# analogControlBoardV1_3.net
KiCad netlist of a schematic drawn in EAGLE
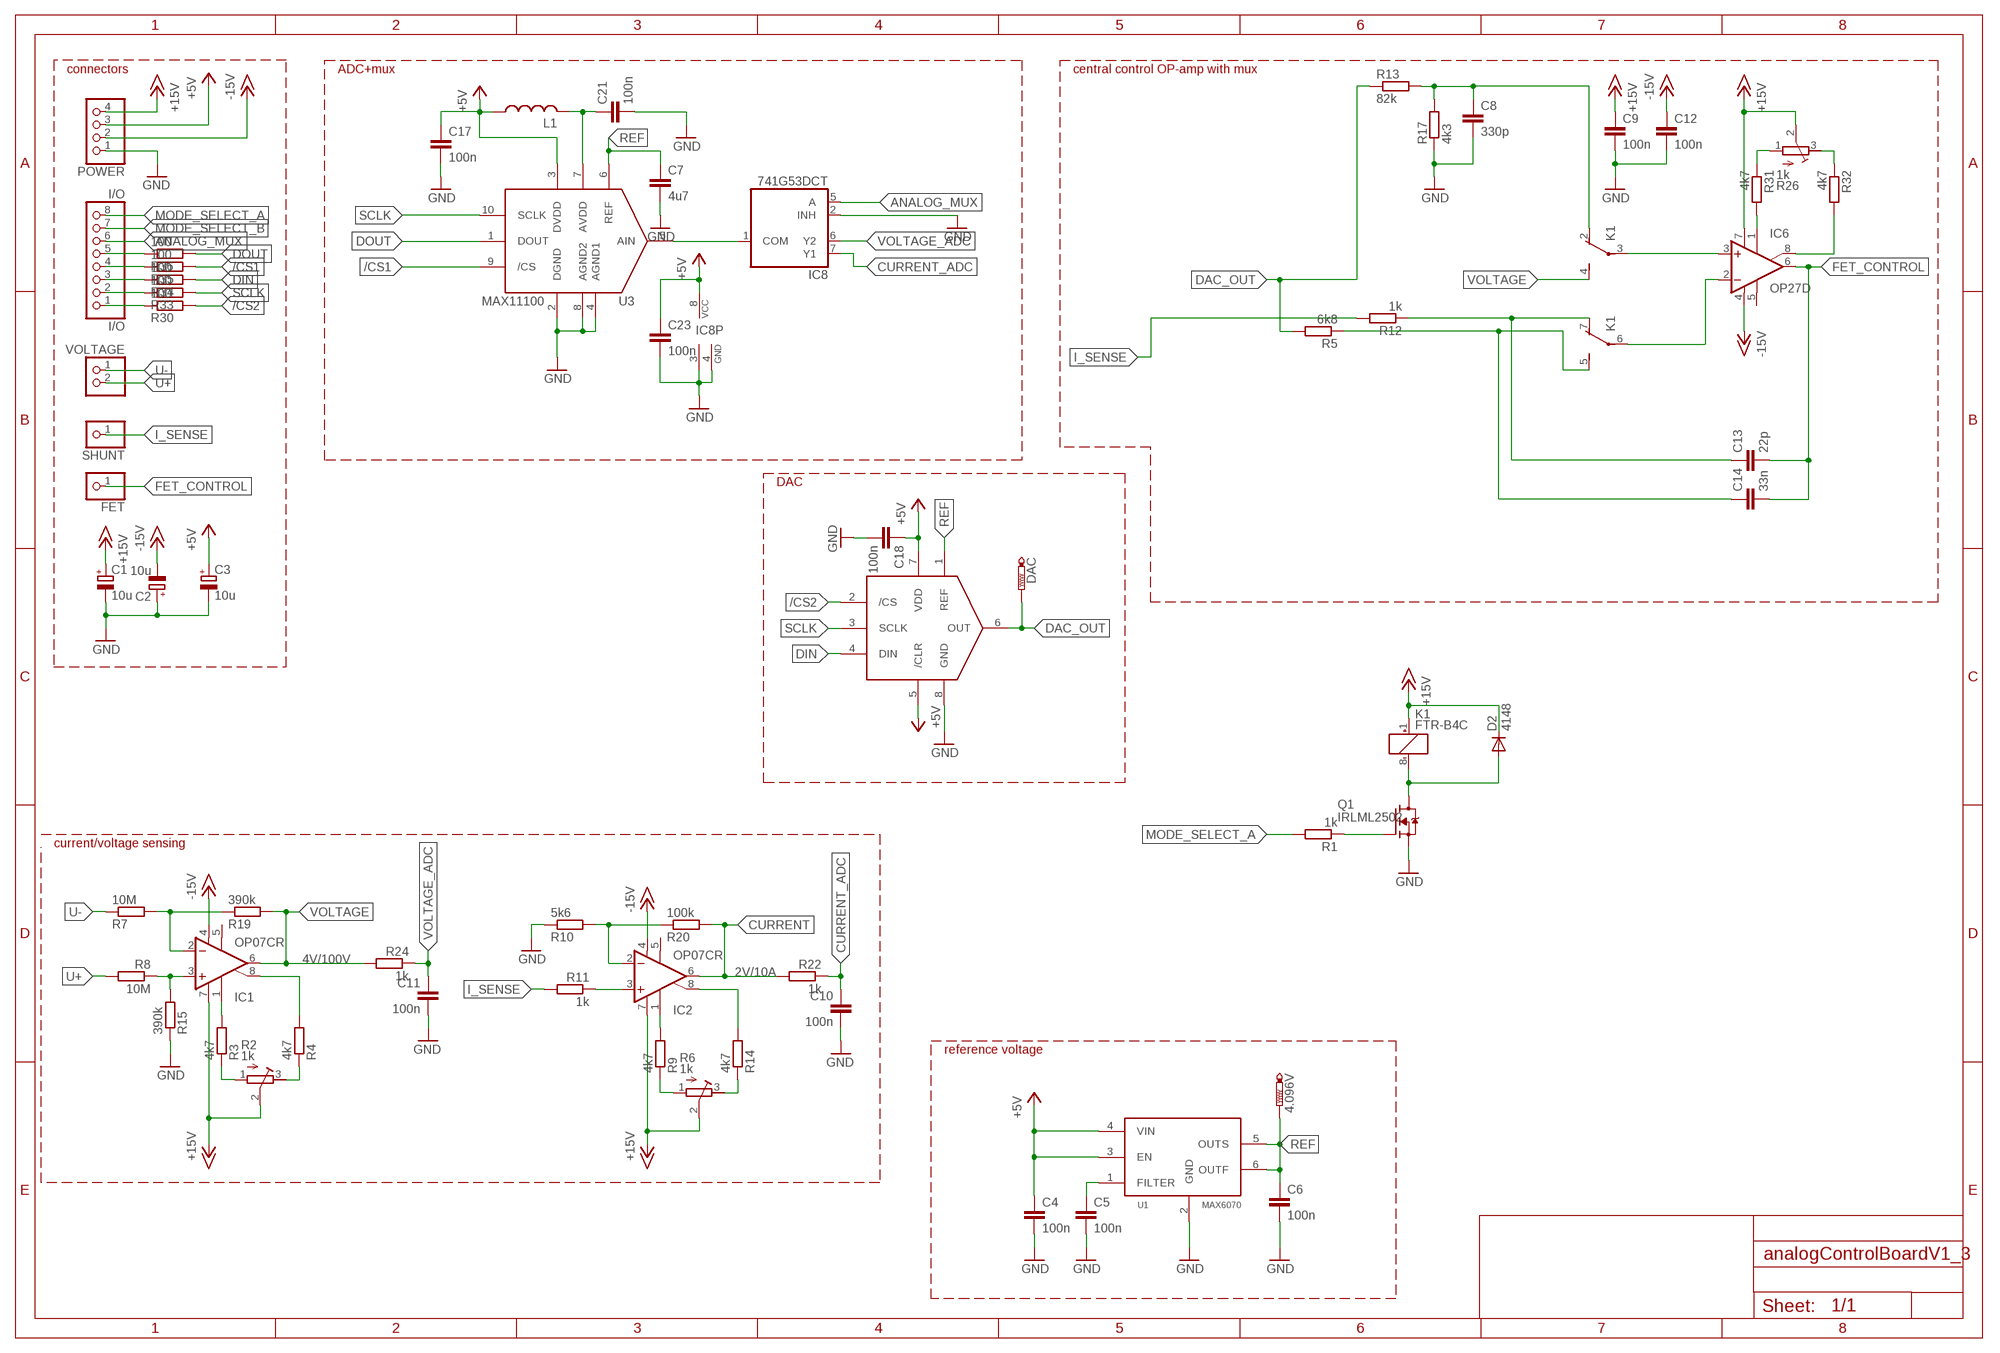
[diagram p0: schematic, sheet 1]

(export (version "E")
  (design (tool "Eeschema 10.0.6"))
  (components
    (comp (ref "4.096V")
      (value "PTR1TP14R")
      (footprint "eagle-import:TP14R")
      (libsource (lib "eagle-import") (part "PTR1TP14R"))
    )
    (comp (ref "C1")
      (value "10u")
      (footprint "eagle-import:153CLV-0505")
      (libsource (lib "eagle-import") (part "CPOL-EU153CLV-0505"))
    )
    (comp (ref "C2")
      (value "10u")
      (footprint "eagle-import:153CLV-0505")
      (libsource (lib "eagle-import") (part "CPOL-EU153CLV-0505"))
    )
    (comp (ref "C3")
      (value "10u")
      (footprint "eagle-import:153CLV-0505")
      (libsource (lib "eagle-import") (part "CPOL-EU153CLV-0505"))
    )
    (comp (ref "C4")
      (value "100n")
      (footprint "eagle-import:C0603K")
      (libsource (lib "eagle-import") (part "C-EUC0603K"))
    )
    (comp (ref "C5")
      (value "100n")
      (footprint "eagle-import:C0603K")
      (libsource (lib "eagle-import") (part "C-EUC0603K"))
    )
    (comp (ref "C6")
      (value "100n")
      (footprint "eagle-import:C0603K")
      (libsource (lib "eagle-import") (part "C-EUC0603K"))
    )
    (comp (ref "C7")
      (value "4u7")
      (footprint "eagle-import:C0805")
      (libsource (lib "eagle-import") (part "C-EUC0805"))
    )
    (comp (ref "C8")
      (value "330p")
      (footprint "eagle-import:C0603K")
      (libsource (lib "eagle-import") (part "C-EUC0603K"))
    )
    (comp (ref "C9")
      (value "100n")
      (footprint "eagle-import:C0603K")
      (libsource (lib "eagle-import") (part "C-EUC0603K"))
    )
    (comp (ref "C10")
      (value "100n")
      (footprint "eagle-import:C0603K")
      (libsource (lib "eagle-import") (part "C-EUC0603K"))
    )
    (comp (ref "C11")
      (value "100n")
      (footprint "eagle-import:C0603K")
      (libsource (lib "eagle-import") (part "C-EUC0603K"))
    )
    (comp (ref "C12")
      (value "100n")
      (footprint "eagle-import:C0603K")
      (libsource (lib "eagle-import") (part "C-EUC0603K"))
    )
    (comp (ref "C13")
      (value "22p")
      (footprint "eagle-import:C0603K")
      (libsource (lib "eagle-import") (part "C-EUC0603K"))
    )
    (comp (ref "C14")
      (value "33n")
      (footprint "eagle-import:C0603K")
      (libsource (lib "eagle-import") (part "C-EUC0603K"))
    )
    (comp (ref "C17")
      (value "100n")
      (footprint "eagle-import:C0603K")
      (libsource (lib "eagle-import") (part "C-EUC0603K"))
    )
    (comp (ref "C18")
      (value "100n")
      (footprint "eagle-import:C0603K")
      (libsource (lib "eagle-import") (part "C-EUC0603K"))
    )
    (comp (ref "C21")
      (value "100n")
      (footprint "eagle-import:C0603K")
      (libsource (lib "eagle-import") (part "C-EUC0603K"))
    )
    (comp (ref "C23")
      (value "100n")
      (footprint "eagle-import:C0603K")
      (libsource (lib "eagle-import") (part "C-EUC0603K"))
    )
    (comp (ref "D2")
      (value "4148")
      (footprint "eagle-import:SOD123")
      (libsource (lib "eagle-import") (part "DIODE-SOD123"))
    )
    (comp (ref "DAC")
      (value "PTR1TP14R")
      (footprint "eagle-import:TP14R")
      (libsource (lib "eagle-import") (part "PTR1TP14R"))
    )
    (comp (ref "FET")
      (value "PINHD-1X1")
      (footprint "eagle-import:1X01")
      (libsource (lib "eagle-import") (part "PINHD-1X1"))
    )
    (comp (ref "I/O")
      (value "I/O")
      (footprint "eagle-import:1X08")
      (libsource (lib "eagle-import") (part "PINHD-1X8"))
    )
    (comp (ref "IC1")
      (value "OP07CR")
      (footprint "eagle-import:SO08")
      (libsource (lib "eagle-import") (part "OP07RC"))
    )
    (comp (ref "IC2")
      (value "OP07CR")
      (footprint "eagle-import:SO08")
      (libsource (lib "eagle-import") (part "OP07RC"))
    )
    (comp (ref "IC6")
      (value "OP27D")
      (footprint "eagle-import:SO08")
      (libsource (lib "eagle-import") (part "OP27D"))
    )
    (comp (ref "IC8")
      (value "741G53DCT")
      (footprint "eagle-import:DCT_R-PDSO-G8")
      (libsource (lib "eagle-import") (part "741G53DCT"))
    )
    (comp (ref "K1")
      (value "FTR-B4C")
      (footprint "eagle-import:FTR-B4C")
      (libsource (lib "eagle-import") (part "FTR-B4C"))
    )
    (comp (ref "L1")
      (value "INDUCTOR0603")
      (footprint "eagle-import:R0603")
      (libsource (lib "eagle-import") (part "INDUCTOR0603"))
    )
    (comp (ref "POWER")
      (value "PINHD-1X4")
      (footprint "eagle-import:1X04")
      (libsource (lib "eagle-import") (part "PINHD-1X4"))
    )
    (comp (ref "Q1")
      (value "IRLML2502")
      (footprint "eagle-import:SOT23-3")
      (libsource (lib "eagle-import") (part "IRLML2502"))
    )
    (comp (ref "R1")
      (value "1k")
      (footprint "eagle-import:R0603")
      (libsource (lib "eagle-import") (part "R-EU_R0603"))
    )
    (comp (ref "R2")
      (value "1k")
      (footprint "eagle-import:RTRIM64W")
      (libsource (lib "eagle-import") (part "R-TRIMM64W"))
    )
    (comp (ref "R3")
      (value "4k7")
      (footprint "eagle-import:R0603")
      (libsource (lib "eagle-import") (part "R-EU_R0603"))
    )
    (comp (ref "R4")
      (value "4k7")
      (footprint "eagle-import:R0603")
      (libsource (lib "eagle-import") (part "R-EU_R0603"))
    )
    (comp (ref "R5")
      (value "6k8")
      (footprint "eagle-import:R0603")
      (libsource (lib "eagle-import") (part "R-EU_R0603"))
    )
    (comp (ref "R6")
      (value "1k")
      (footprint "eagle-import:RTRIM64W")
      (libsource (lib "eagle-import") (part "R-TRIMM64W"))
    )
    (comp (ref "R7")
      (value "10M")
      (footprint "eagle-import:R0603")
      (libsource (lib "eagle-import") (part "R-EU_R0603"))
    )
    (comp (ref "R8")
      (value "10M")
      (footprint "eagle-import:R0603")
      (libsource (lib "eagle-import") (part "R-EU_R0603"))
    )
    (comp (ref "R9")
      (value "4k7")
      (footprint "eagle-import:R0603")
      (libsource (lib "eagle-import") (part "R-EU_R0603"))
    )
    (comp (ref "R10")
      (value "5k6")
      (footprint "eagle-import:R0603")
      (libsource (lib "eagle-import") (part "R-EU_R0603"))
    )
    (comp (ref "R11")
      (value "1k")
      (footprint "eagle-import:R0603")
      (libsource (lib "eagle-import") (part "R-EU_R0603"))
    )
    (comp (ref "R12")
      (value "1k")
      (footprint "eagle-import:R0603")
      (libsource (lib "eagle-import") (part "R-EU_R0603"))
    )
    (comp (ref "R13")
      (value "82k")
      (footprint "eagle-import:R0603")
      (libsource (lib "eagle-import") (part "R-EU_R0603"))
    )
    (comp (ref "R14")
      (value "4k7")
      (footprint "eagle-import:R0603")
      (libsource (lib "eagle-import") (part "R-EU_R0603"))
    )
    (comp (ref "R15")
      (value "390k")
      (footprint "eagle-import:R0603")
      (libsource (lib "eagle-import") (part "R-EU_R0603"))
    )
    (comp (ref "R17")
      (value "4k3")
      (footprint "eagle-import:R0603")
      (libsource (lib "eagle-import") (part "R-EU_R0603"))
    )
    (comp (ref "R19")
      (value "390k")
      (footprint "eagle-import:R0603")
      (libsource (lib "eagle-import") (part "R-EU_R0603"))
    )
    (comp (ref "R20")
      (value "100k")
      (footprint "eagle-import:R0603")
      (libsource (lib "eagle-import") (part "R-EU_R0603"))
    )
    (comp (ref "R22")
      (value "1k")
      (footprint "eagle-import:R0603")
      (libsource (lib "eagle-import") (part "R-EU_R0603"))
    )
    (comp (ref "R24")
      (value "1k")
      (footprint "eagle-import:R0603")
      (libsource (lib "eagle-import") (part "R-EU_R0603"))
    )
    (comp (ref "R26")
      (value "1k")
      (footprint "eagle-import:RTRIM64W")
      (libsource (lib "eagle-import") (part "R-TRIMM64W"))
    )
    (comp (ref "R30")
      (value "100")
      (footprint "eagle-import:R0603")
      (libsource (lib "eagle-import") (part "R-EU_R0603"))
    )
    (comp (ref "R31")
      (value "4k7")
      (footprint "eagle-import:R0603")
      (libsource (lib "eagle-import") (part "R-EU_R0603"))
    )
    (comp (ref "R32")
      (value "4k7")
      (footprint "eagle-import:R0603")
      (libsource (lib "eagle-import") (part "R-EU_R0603"))
    )
    (comp (ref "R33")
      (value "100")
      (footprint "eagle-import:R0603")
      (libsource (lib "eagle-import") (part "R-EU_R0603"))
    )
    (comp (ref "R34")
      (value "100")
      (footprint "eagle-import:R0603")
      (libsource (lib "eagle-import") (part "R-EU_R0603"))
    )
    (comp (ref "R35")
      (value "100")
      (footprint "eagle-import:R0603")
      (libsource (lib "eagle-import") (part "R-EU_R0603"))
    )
    (comp (ref "R36")
      (value "100")
      (footprint "eagle-import:R0603")
      (libsource (lib "eagle-import") (part "R-EU_R0603"))
    )
    (comp (ref "SHUNT")
      (value "PINHD-1X1")
      (footprint "eagle-import:1X01")
      (libsource (lib "eagle-import") (part "PINHD-1X1"))
    )
    (comp (ref "U1")
      (value "MAX6070")
      (footprint "eagle-import:SOT23-6L")
      (libsource (lib "eagle-import") (part "MAX6070"))
    )
    (comp (ref "U2")
      (value "MAX5216")
      (footprint "eagle-import:UMAX8")
      (libsource (lib "eagle-import") (part "MAX5216"))
    )
    (comp (ref "U3")
      (value "MAX11100")
      (footprint "eagle-import:UMAX10")
      (libsource (lib "eagle-import") (part "MAX11100"))
    )
    (comp (ref "VOLTAGE")
      (value "PINHD-1X2")
      (footprint "eagle-import:1X02")
      (libsource (lib "eagle-import") (part "PINHD-1X2"))
    )
  )
  (nets
    (net (code "1") (name "+5V") (class "Default")
      (node (ref "C17") (pin "1") (pinfunction "1_1") (pintype "passive"))
      (node (ref "C18") (pin "1") (pinfunction "1_1") (pintype "passive"))
      (node (ref "C23") (pin "1") (pinfunction "1_1") (pintype "passive"))
      (node (ref "C3") (pin "+") (pinfunction "+_+") (pintype "passive"))
      (node (ref "C4") (pin "1") (pinfunction "1_1") (pintype "passive"))
      (node (ref "IC8") (pin "8") (pinfunction "VCC_8") (pintype "power_in"))
      (node (ref "L1") (pin "1") (pinfunction "1_1") (pintype "passive"))
      (node (ref "POWER") (pin "3") (pinfunction "3_3") (pintype "passive"))
      (node (ref "U1") (pin "3") (pinfunction "EN_3") (pintype "bidirectional"))
      (node (ref "U1") (pin "4") (pinfunction "VIN_4") (pintype "bidirectional"))
      (node (ref "U2") (pin "5") (pinfunction "/CLR_5") (pintype "bidirectional"))
      (node (ref "U2") (pin "7") (pinfunction "VDD_7") (pintype "bidirectional"))
      (node (ref "U3") (pin "3") (pinfunction "DVDD_3") (pintype "bidirectional"))
    )
    (net (code "2") (name "+15V") (class "Default")
      (node (ref "C1") (pin "+") (pinfunction "+_+") (pintype "passive"))
      (node (ref "C9") (pin "1") (pinfunction "1_1") (pintype "passive"))
      (node (ref "D2") (pin "C") (pinfunction "C_C") (pintype "passive"))
      (node (ref "IC1") (pin "7") (pinfunction "V+_7") (pintype "power_in"))
      (node (ref "IC2") (pin "7") (pinfunction "V+_7") (pintype "power_in"))
      (node (ref "IC6") (pin "7") (pinfunction "V+_7") (pintype "power_in"))
      (node (ref "K1") (pin "1") (pinfunction "+_1") (pintype "passive"))
      (node (ref "POWER") (pin "4") (pinfunction "4_4") (pintype "passive"))
      (node (ref "R2") (pin "2") (pinfunction "S_2") (pintype "passive"))
      (node (ref "R26") (pin "2") (pinfunction "S_2") (pintype "passive"))
      (node (ref "R6") (pin "2") (pinfunction "S_2") (pintype "passive"))
    )
    (net (code "3") (name "-15V") (class "Default")
      (node (ref "C12") (pin "1") (pinfunction "1_1") (pintype "passive"))
      (node (ref "C2") (pin "-") (pinfunction "-_-") (pintype "passive"))
      (node (ref "IC1") (pin "4") (pinfunction "V-_4") (pintype "power_in"))
      (node (ref "IC2") (pin "4") (pinfunction "V-_4") (pintype "power_in"))
      (node (ref "IC6") (pin "4") (pinfunction "V-_4") (pintype "power_in"))
      (node (ref "POWER") (pin "2") (pinfunction "2_2") (pintype "passive"))
    )
    (net (code "4") (name "ANALOG_MUX") (class "Default")
      (node (ref "I/O") (pin "6") (pinfunction "6_6") (pintype "passive"))
      (node (ref "IC8") (pin "5") (pinfunction "A_5") (pintype "input"))
    )
    (net (code "5") (name "CURRENT") (class "Default")
      (node (ref "IC2") (pin "6") (pinfunction "OUT_6") (pintype "output"))
      (node (ref "R20") (pin "2") (pinfunction "2_2") (pintype "passive"))
      (node (ref "R22") (pin "2") (pinfunction "2_2") (pintype "passive"))
    )
    (net (code "6") (name "CURRENT_ADC") (class "Default")
      (node (ref "C10") (pin "1") (pinfunction "1_1") (pintype "passive"))
      (node (ref "IC8") (pin "7") (pinfunction "Y1_7") (pintype "bidirectional"))
      (node (ref "R22") (pin "1") (pinfunction "1_1") (pintype "passive"))
    )
    (net (code "7") (name "DAC_OUT") (class "Default")
      (node (ref "DAC") (pin "TP") (pinfunction "TP_TP") (pintype "input"))
      (node (ref "R13") (pin "1") (pinfunction "1_1") (pintype "passive"))
      (node (ref "R5") (pin "2") (pinfunction "2_2") (pintype "passive"))
      (node (ref "U2") (pin "6") (pinfunction "OUT_6") (pintype "bidirectional"))
    )
    (net (code "8") (name "DIN") (class "Default")
      (node (ref "R34") (pin "2") (pinfunction "2_2") (pintype "passive"))
      (node (ref "U2") (pin "4") (pinfunction "DIN_4") (pintype "bidirectional"))
    )
    (net (code "9") (name "DOUT") (class "Default")
      (node (ref "R36") (pin "2") (pinfunction "2_2") (pintype "passive"))
      (node (ref "U3") (pin "1") (pinfunction "DOUT_1") (pintype "bidirectional"))
    )
    (net (code "10") (name "FET_CONTROL") (class "Default")
      (node (ref "C13") (pin "2") (pinfunction "2_2") (pintype "passive"))
      (node (ref "C14") (pin "2") (pinfunction "2_2") (pintype "passive"))
      (node (ref "FET") (pin "1") (pinfunction "1_1") (pintype "passive"))
      (node (ref "IC6") (pin "6") (pinfunction "OUT_6") (pintype "output"))
    )
    (net (code "11") (name "GND") (class "Default")
      (node (ref "C1") (pin "-") (pinfunction "-_-") (pintype "passive"))
      (node (ref "C10") (pin "2") (pinfunction "2_2") (pintype "passive"))
      (node (ref "C11") (pin "2") (pinfunction "2_2") (pintype "passive"))
      (node (ref "C12") (pin "2") (pinfunction "2_2") (pintype "passive"))
      (node (ref "C17") (pin "2") (pinfunction "2_2") (pintype "passive"))
      (node (ref "C18") (pin "2") (pinfunction "2_2") (pintype "passive"))
      (node (ref "C2") (pin "+") (pinfunction "+_+") (pintype "passive"))
      (node (ref "C21") (pin "2") (pinfunction "2_2") (pintype "passive"))
      (node (ref "C23") (pin "2") (pinfunction "2_2") (pintype "passive"))
      (node (ref "C3") (pin "-") (pinfunction "-_-") (pintype "passive"))
      (node (ref "C4") (pin "2") (pinfunction "2_2") (pintype "passive"))
      (node (ref "C5") (pin "2") (pinfunction "2_2") (pintype "passive"))
      (node (ref "C6") (pin "2") (pinfunction "2_2") (pintype "passive"))
      (node (ref "C7") (pin "2") (pinfunction "2_2") (pintype "passive"))
      (node (ref "C8") (pin "2") (pinfunction "2_2") (pintype "passive"))
      (node (ref "C9") (pin "2") (pinfunction "2_2") (pintype "passive"))
      (node (ref "IC8") (pin "2") (pinfunction "INH_2") (pintype "input"))
      (node (ref "IC8") (pin "3") (pinfunction "GND_3") (pintype "power_in"))
      (node (ref "IC8") (pin "4") (pinfunction "GND_4") (pintype "power_in"))
      (node (ref "POWER") (pin "1") (pinfunction "1_1") (pintype "passive"))
      (node (ref "Q1") (pin "2") (pinfunction "S_2") (pintype "passive"))
      (node (ref "R10") (pin "1") (pinfunction "1_1") (pintype "passive"))
      (node (ref "R15") (pin "1") (pinfunction "1_1") (pintype "passive"))
      (node (ref "R17") (pin "1") (pinfunction "1_1") (pintype "passive"))
      (node (ref "U1") (pin "2") (pinfunction "GND_2") (pintype "bidirectional"))
      (node (ref "U2") (pin "8") (pinfunction "GND_8") (pintype "bidirectional"))
      (node (ref "U3") (pin "2") (pinfunction "DGND_2") (pintype "bidirectional"))
      (node (ref "U3") (pin "4") (pinfunction "AGND1_4") (pintype "bidirectional"))
      (node (ref "U3") (pin "8") (pinfunction "AGND2_8") (pintype "bidirectional"))
    )
    (net (code "12") (name "I_SENSE") (class "Default")
      (node (ref "R11") (pin "2") (pinfunction "2_2") (pintype "passive"))
      (node (ref "R12") (pin "2") (pinfunction "2_2") (pintype "passive"))
      (node (ref "SHUNT") (pin "1") (pinfunction "1_1") (pintype "passive"))
    )
    (net (code "13") (name "MODE_SELECT_A") (class "Default")
      (node (ref "I/O") (pin "8") (pinfunction "8_8") (pintype "passive"))
      (node (ref "R1") (pin "2") (pinfunction "2_2") (pintype "passive"))
    )
    (net (code "14") (name "MODE_SELECT_B") (class "Default")
      (node (ref "I/O") (pin "7") (pinfunction "7_7") (pintype "passive"))
    )
    (net (code "15") (name "Net-(I/O-Pad1)") (class "Default")
      (node (ref "I/O") (pin "1") (pinfunction "1_1") (pintype "passive"))
      (node (ref "R30") (pin "1") (pinfunction "1_1") (pintype "passive"))
    )
    (net (code "16") (name "Net-(I/O-Pad2)") (class "Default")
      (node (ref "I/O") (pin "2") (pinfunction "2_2") (pintype "passive"))
      (node (ref "R33") (pin "1") (pinfunction "1_1") (pintype "passive"))
    )
    (net (code "17") (name "Net-(I/O-Pad3)") (class "Default")
      (node (ref "I/O") (pin "3") (pinfunction "3_3") (pintype "passive"))
      (node (ref "R34") (pin "1") (pinfunction "1_1") (pintype "passive"))
    )
    (net (code "18") (name "Net-(I/O-Pad4)") (class "Default")
      (node (ref "I/O") (pin "4") (pinfunction "4_4") (pintype "passive"))
      (node (ref "R35") (pin "1") (pinfunction "1_1") (pintype "passive"))
    )
    (net (code "19") (name "Net-(I/O-Pad5)") (class "Default")
      (node (ref "I/O") (pin "5") (pinfunction "5_5") (pintype "passive"))
      (node (ref "R36") (pin "1") (pinfunction "1_1") (pintype "passive"))
    )
    (net (code "20") (name "Net-(IC1-+IN)") (class "Default")
      (node (ref "IC1") (pin "3") (pinfunction "+IN_3") (pintype "input"))
      (node (ref "R15") (pin "2") (pinfunction "2_2") (pintype "passive"))
      (node (ref "R8") (pin "1") (pinfunction "1_1") (pintype "passive"))
    )
    (net (code "21") (name "Net-(IC1--IN)") (class "Default")
      (node (ref "IC1") (pin "2") (pinfunction "-IN_2") (pintype "input"))
      (node (ref "R19") (pin "1") (pinfunction "1_1") (pintype "passive"))
      (node (ref "R7") (pin "2") (pinfunction "2_2") (pintype "passive"))
    )
    (net (code "22") (name "Net-(IC1-ON1)") (class "Default")
      (node (ref "IC1") (pin "1") (pinfunction "ON1_1") (pintype "passive"))
      (node (ref "R3") (pin "2") (pinfunction "2_2") (pintype "passive"))
    )
    (net (code "23") (name "Net-(IC1-ON2)") (class "Default")
      (node (ref "IC1") (pin "8") (pinfunction "ON2_8") (pintype "passive"))
      (node (ref "R4") (pin "2") (pinfunction "2_2") (pintype "passive"))
    )
    (net (code "24") (name "Net-(IC2-+IN)") (class "Default")
      (node (ref "IC2") (pin "3") (pinfunction "+IN_3") (pintype "input"))
      (node (ref "R11") (pin "1") (pinfunction "1_1") (pintype "passive"))
    )
    (net (code "25") (name "Net-(IC2--IN)") (class "Default")
      (node (ref "IC2") (pin "2") (pinfunction "-IN_2") (pintype "input"))
      (node (ref "R10") (pin "2") (pinfunction "2_2") (pintype "passive"))
      (node (ref "R20") (pin "1") (pinfunction "1_1") (pintype "passive"))
    )
    (net (code "26") (name "Net-(IC2-ON1)") (class "Default")
      (node (ref "IC2") (pin "1") (pinfunction "ON1_1") (pintype "passive"))
      (node (ref "R9") (pin "2") (pinfunction "2_2") (pintype "passive"))
    )
    (net (code "27") (name "Net-(IC2-ON2)") (class "Default")
      (node (ref "IC2") (pin "8") (pinfunction "ON2_8") (pintype "passive"))
      (node (ref "R14") (pin "2") (pinfunction "2_2") (pintype "passive"))
    )
    (net (code "28") (name "Net-(IC6-+IN)") (class "Default")
      (node (ref "IC6") (pin "3") (pinfunction "+IN_3") (pintype "input"))
      (node (ref "K1") (pin "3") (pinfunction "P_3") (pintype "passive"))
    )
    (net (code "29") (name "Net-(IC6--IN)") (class "Default")
      (node (ref "IC6") (pin "2") (pinfunction "-IN_2") (pintype "input"))
      (node (ref "K1") (pin "6") (pinfunction "P_6") (pintype "passive"))
    )
    (net (code "30") (name "Net-(IC6-ON1)") (class "Default")
      (node (ref "IC6") (pin "1") (pinfunction "ON1_1") (pintype "passive"))
      (node (ref "R31") (pin "2") (pinfunction "2_2") (pintype "passive"))
    )
    (net (code "31") (name "Net-(IC6-ON2)") (class "Default")
      (node (ref "IC6") (pin "8") (pinfunction "ON2_8") (pintype "passive"))
      (node (ref "R32") (pin "2") (pinfunction "2_2") (pintype "passive"))
    )
    (net (code "32") (name "Net-(IC8A-COM)") (class "Default")
      (node (ref "IC8") (pin "1") (pinfunction "COM_1") (pintype "bidirectional"))
      (node (ref "U3") (pin "5") (pinfunction "AIN_5") (pintype "bidirectional"))
    )
    (net (code "33") (name "Net-(K1A-O)") (class "Default")
      (node (ref "C8") (pin "1") (pinfunction "1_1") (pintype "passive"))
      (node (ref "K1") (pin "2") (pinfunction "O_2") (pintype "passive"))
      (node (ref "R13") (pin "2") (pinfunction "2_2") (pintype "passive"))
      (node (ref "R17") (pin "2") (pinfunction "2_2") (pintype "passive"))
    )
    (net (code "34") (name "Net-(K1B-O)") (class "Default")
      (node (ref "C13") (pin "1") (pinfunction "1_1") (pintype "passive"))
      (node (ref "K1") (pin "7") (pinfunction "O_7") (pintype "passive"))
      (node (ref "R12") (pin "1") (pinfunction "1_1") (pintype "passive"))
    )
    (net (code "35") (name "Net-(K1B-S)") (class "Default")
      (node (ref "C14") (pin "1") (pinfunction "1_1") (pintype "passive"))
      (node (ref "K1") (pin "5") (pinfunction "S_5") (pintype "passive"))
      (node (ref "R5") (pin "1") (pinfunction "1_1") (pintype "passive"))
    )
    (net (code "36") (name "Net-(K1C--)") (class "Default")
      (node (ref "D2") (pin "A") (pinfunction "A_A") (pintype "passive"))
      (node (ref "K1") (pin "8") (pinfunction "-_8") (pintype "passive"))
      (node (ref "Q1") (pin "3") (pinfunction "D_3") (pintype "passive"))
    )
    (net (code "37") (name "Net-(Q1-G)") (class "Default")
      (node (ref "Q1") (pin "1") (pinfunction "G_1") (pintype "passive"))
      (node (ref "R1") (pin "1") (pinfunction "1_1") (pintype "passive"))
    )
    (net (code "38") (name "Net-(R2-A)") (class "Default")
      (node (ref "R2") (pin "3") (pinfunction "A_3") (pintype "passive"))
      (node (ref "R4") (pin "1") (pinfunction "1_1") (pintype "passive"))
    )
    (net (code "39") (name "Net-(R2-E)") (class "Default")
      (node (ref "R2") (pin "1") (pinfunction "E_1") (pintype "passive"))
      (node (ref "R3") (pin "1") (pinfunction "1_1") (pintype "passive"))
    )
    (net (code "40") (name "Net-(R6-A)") (class "Default")
      (node (ref "R14") (pin "1") (pinfunction "1_1") (pintype "passive"))
      (node (ref "R6") (pin "3") (pinfunction "A_3") (pintype "passive"))
    )
    (net (code "41") (name "Net-(R6-E)") (class "Default")
      (node (ref "R6") (pin "1") (pinfunction "E_1") (pintype "passive"))
      (node (ref "R9") (pin "1") (pinfunction "1_1") (pintype "passive"))
    )
    (net (code "42") (name "Net-(R26-A)") (class "Default")
      (node (ref "R26") (pin "3") (pinfunction "A_3") (pintype "passive"))
      (node (ref "R32") (pin "1") (pinfunction "1_1") (pintype "passive"))
    )
    (net (code "43") (name "Net-(R26-E)") (class "Default")
      (node (ref "R26") (pin "1") (pinfunction "E_1") (pintype "passive"))
      (node (ref "R31") (pin "1") (pinfunction "1_1") (pintype "passive"))
    )
    (net (code "44") (name "Net-(U1-FILTER)") (class "Default")
      (node (ref "C5") (pin "1") (pinfunction "1_1") (pintype "passive"))
      (node (ref "U1") (pin "1") (pinfunction "FILTER_1") (pintype "bidirectional"))
    )
    (net (code "45") (name "Net-(U3-AVDD)") (class "Default")
      (node (ref "C21") (pin "1") (pinfunction "1_1") (pintype "passive"))
      (node (ref "L1") (pin "2") (pinfunction "2_2") (pintype "passive"))
      (node (ref "U3") (pin "7") (pinfunction "AVDD_7") (pintype "bidirectional"))
    )
    (net (code "46") (name "REF") (class "Default")
      (node (ref "4.096V") (pin "TP") (pinfunction "TP_TP") (pintype "input"))
      (node (ref "C6") (pin "1") (pinfunction "1_1") (pintype "passive"))
      (node (ref "C7") (pin "1") (pinfunction "1_1") (pintype "passive"))
      (node (ref "U1") (pin "5") (pinfunction "OUTS_5") (pintype "bidirectional"))
      (node (ref "U1") (pin "6") (pinfunction "OUTF_6") (pintype "bidirectional"))
      (node (ref "U2") (pin "1") (pinfunction "REF_1") (pintype "bidirectional"))
      (node (ref "U3") (pin "6") (pinfunction "REF_6") (pintype "bidirectional"))
    )
    (net (code "47") (name "SCLK") (class "Default")
      (node (ref "R33") (pin "2") (pinfunction "2_2") (pintype "passive"))
      (node (ref "U2") (pin "3") (pinfunction "SCLK_3") (pintype "bidirectional"))
      (node (ref "U3") (pin "10") (pinfunction "SCLK_10") (pintype "bidirectional"))
    )
    (net (code "48") (name "U+") (class "Default")
      (node (ref "R8") (pin "2") (pinfunction "2_2") (pintype "passive"))
      (node (ref "VOLTAGE") (pin "2") (pinfunction "2_2") (pintype "passive"))
    )
    (net (code "49") (name "U-") (class "Default")
      (node (ref "R7") (pin "1") (pinfunction "1_1") (pintype "passive"))
      (node (ref "VOLTAGE") (pin "1") (pinfunction "1_1") (pintype "passive"))
    )
    (net (code "50") (name "VOLTAGE") (class "Default")
      (node (ref "IC1") (pin "6") (pinfunction "OUT_6") (pintype "output"))
      (node (ref "K1") (pin "4") (pinfunction "S_4") (pintype "passive"))
      (node (ref "R19") (pin "2") (pinfunction "2_2") (pintype "passive"))
      (node (ref "R24") (pin "2") (pinfunction "2_2") (pintype "passive"))
    )
    (net (code "51") (name "VOLTAGE_ADC") (class "Default")
      (node (ref "C11") (pin "1") (pinfunction "1_1") (pintype "passive"))
      (node (ref "IC8") (pin "6") (pinfunction "Y2_6") (pintype "bidirectional"))
      (node (ref "R24") (pin "1") (pinfunction "1_1") (pintype "passive"))
    )
    (net (code "52") (name "unconnected-(IC1-OPT-Pad5)") (class "Default")
      (node (ref "IC1") (pin "5") (pinfunction "OPT_5") (pintype "passive"))
    )
    (net (code "53") (name "unconnected-(IC2-OPT-Pad5)") (class "Default")
      (node (ref "IC2") (pin "5") (pinfunction "OPT_5") (pintype "passive"))
    )
    (net (code "54") (name "unconnected-(IC6-OPT-Pad5)") (class "Default")
      (node (ref "IC6") (pin "5") (pinfunction "OPT_5") (pintype "passive"))
    )
    (net (code "55") (name "{slash}CS1") (class "Default")
      (node (ref "R35") (pin "2") (pinfunction "2_2") (pintype "passive"))
      (node (ref "U3") (pin "9") (pinfunction "/CS_9") (pintype "bidirectional"))
    )
    (net (code "56") (name "{slash}CS2") (class "Default")
      (node (ref "R30") (pin "2") (pinfunction "2_2") (pintype "passive"))
      (node (ref "U2") (pin "2") (pinfunction "/CS_2") (pintype "bidirectional"))
    )
  )
)
